# MCU.net
KiCad netlist of a schematic drawn in Altium Designer
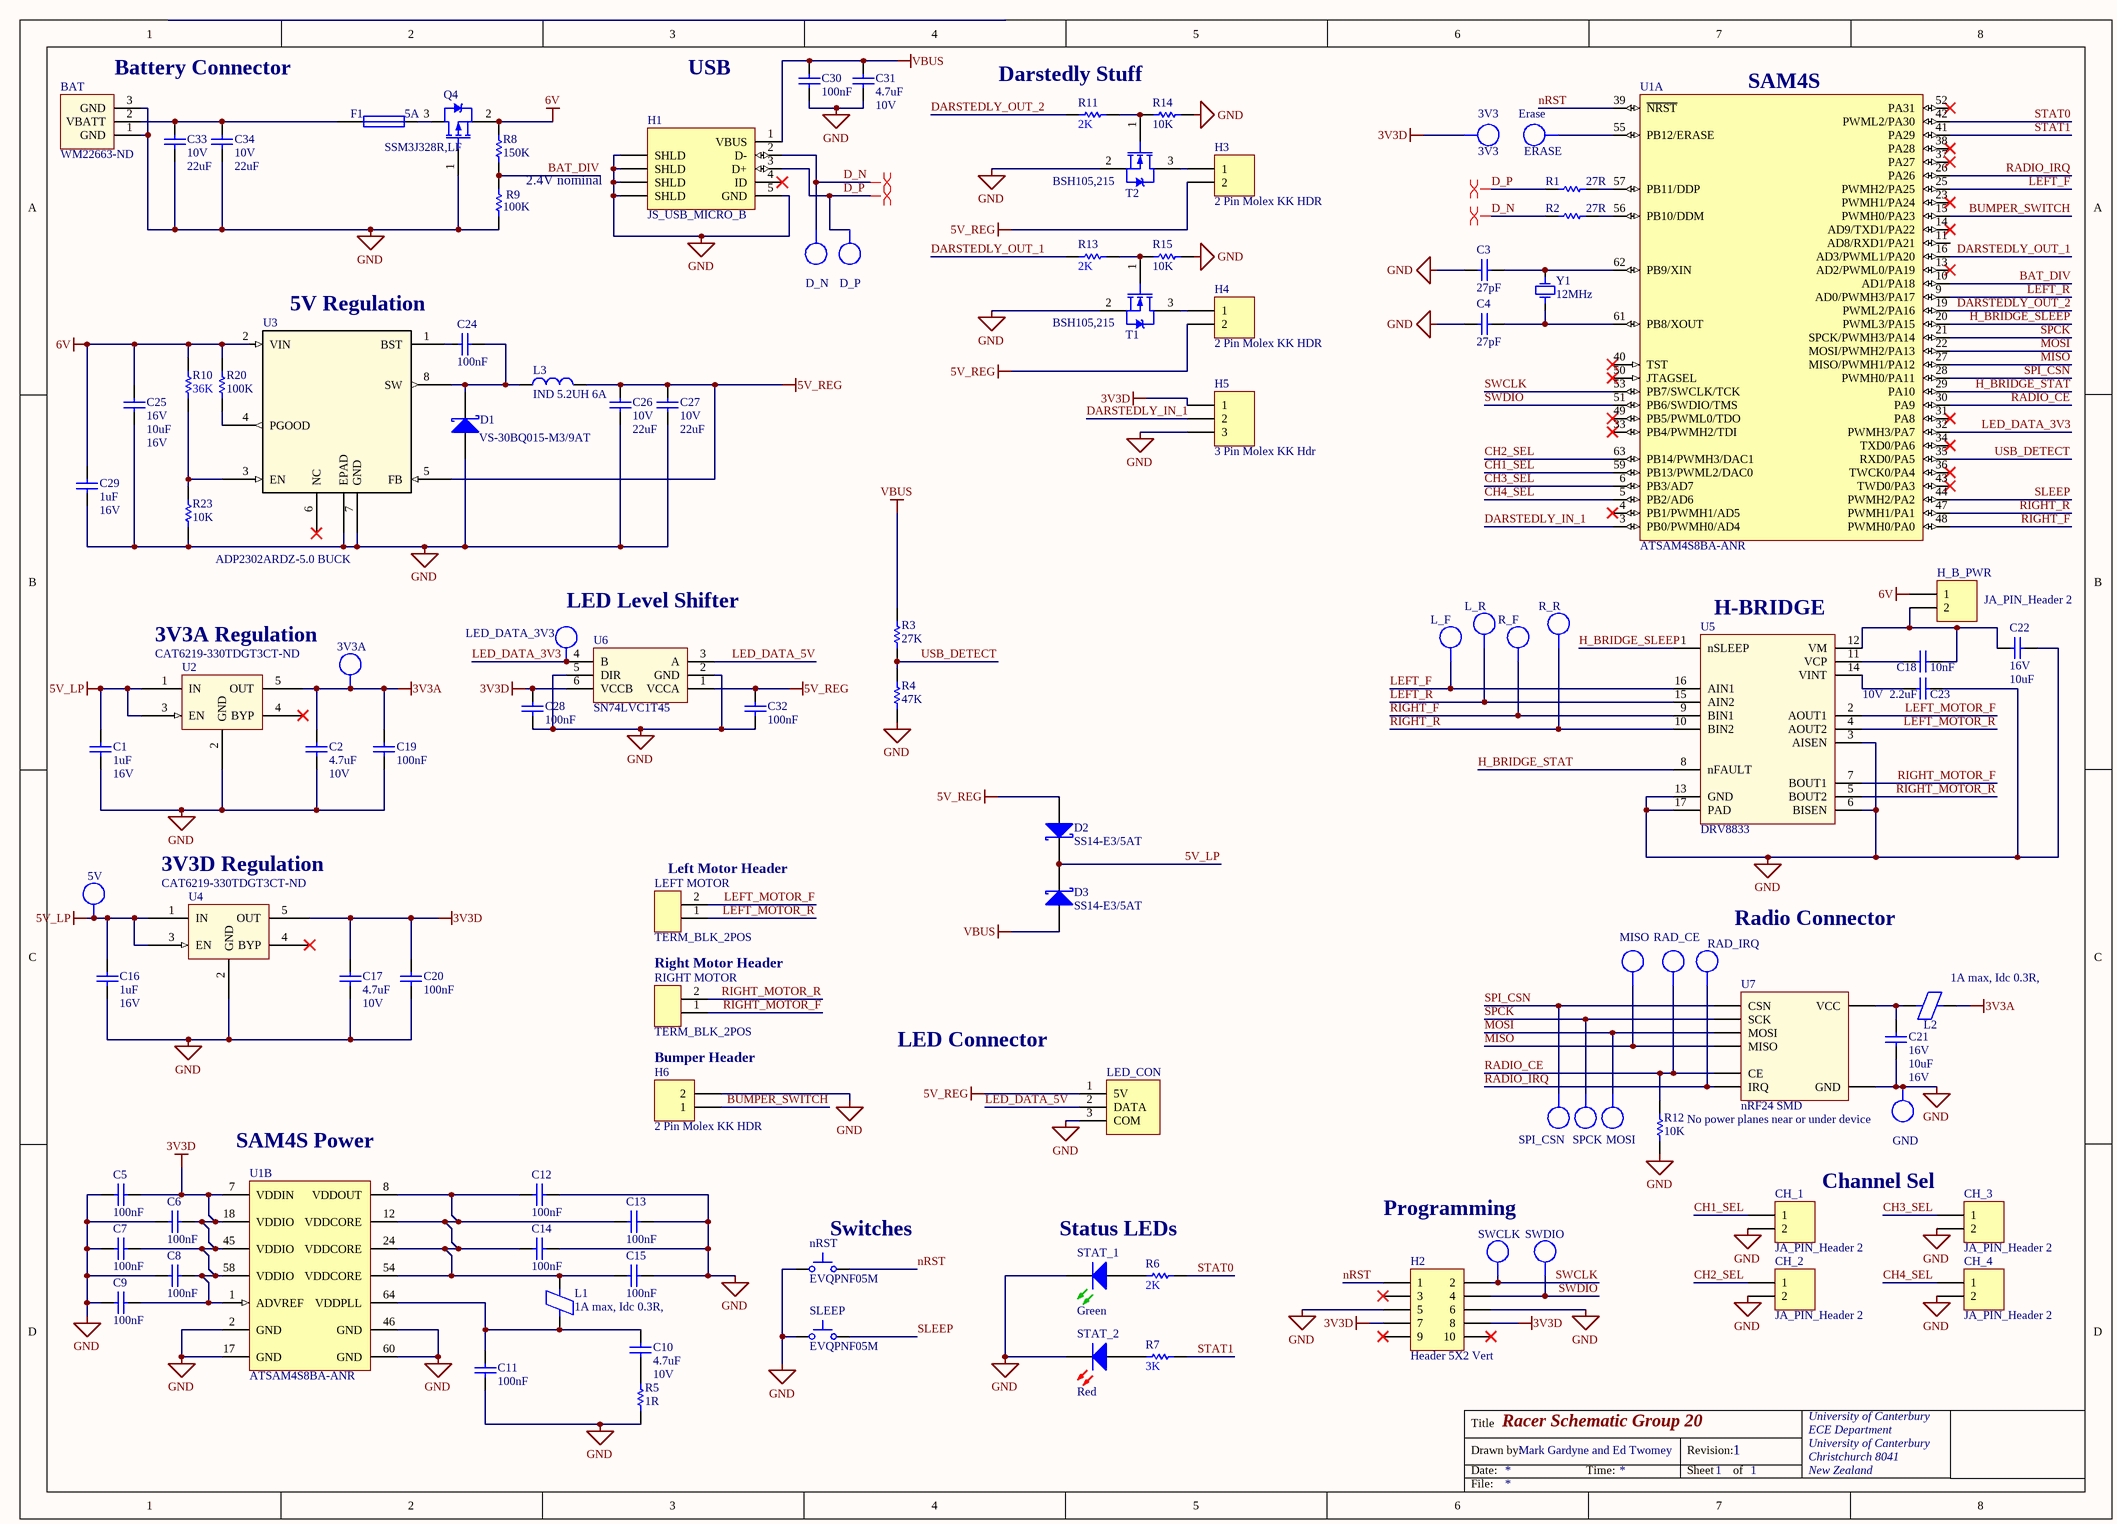
[diagram p0: MCU.SchDoc]

(export (version "E")
  (design (tool "Eeschema 10.0.6"))
  (components
    (comp (ref "3V3")
      (value "3V3")
      (footprint "TP_1206")
      (description "Test-Point 3.3x1.6x2.1mm SMD")
      (fields
        (field (name "MANUFACTURER") "Harwin Inc")
        (field (name "MANUFACTURER PART NUMBER") "S1751-46R")
      )
      (libsource (lib "ECE AD19Components_22V1") (part "TP_1206"))
    )
    (comp (ref "3V3A")
      (value "TP")
      (footprint "TP_1206")
      (description "Test-Point 3.3x1.6x2.1mm SMD")
      (fields
        (field (name "MANUFACTURER") "Harwin Inc")
        (field (name "MANUFACTURER PART NUMBER") "S1751-46R")
      )
      (libsource (lib "ECE AD19Components_22V1") (part "TP_1206"))
    )
    (comp (ref "5V")
      (value "TP")
      (footprint "TP_1206")
      (description "Test-Point 3.3x1.6x2.1mm SMD")
      (fields
        (field (name "MANUFACTURER") "Harwin Inc")
        (field (name "MANUFACTURER PART NUMBER") "S1751-46R")
      )
      (libsource (lib "ECE AD19Components_22V1") (part "TP_1206"))
    )
    (comp (ref "BAT")
      (value "Battery_HEADER_3pin")
      (footprint "BATT_HEADER_3POS")
      (description "3Pin Header 2.54mm spacing\r\nDigikey #WM22663-ND")
      (fields (field (name "SUPPLIER PART NUMBER 1") "WM22663-ND"))
      (libsource (lib "ENCE461AD19_V22") (part "Battery_HEADER_3pin"))
    )
    (comp (ref "C1")
      (value "1uF")
      (footprint "CAPC1608L")
      (description "CAP CER 1uF Y5V -20% +80% 16V 0603")
      (fields (field (name "MAX VOLTAGE") "16V"))
      (libsource (lib "ECE AD19Components_22V1") (part "CC_1uF_0603"))
    )
    (comp (ref "C2")
      (value "4.7uF")
      (footprint "CAPC1608N")
      (description "CAP CER 4.7uF X5R +-20%  10V 0603")
      (fields (field (name "MAX VOLTAGE") "10V"))
      (libsource (lib "ECE AD19Components_22V1") (part "CC_4.7uF_0603"))
    )
    (comp (ref "C3")
      (value "27pF")
      (footprint "CAPC1608L")
      (description "CAP CER 27pF NPO/COG +-5% 50V 0603")
      (libsource (lib "ECE AD19Components_22V1") (part "CC_27pF_0603"))
    )
    (comp (ref "C4")
      (value "27pF")
      (footprint "CAPC1608L")
      (description "CAP CER 27pF NPO/COG +-5% 50V 0603")
      (libsource (lib "ECE AD19Components_22V1") (part "CC_27pF_0603"))
    )
    (comp (ref "C5")
      (value "100nF")
      (footprint "CAPC1608L")
      (description "CAP CER 100nF X7R +-10% 50V 0603")
      (libsource (lib "ECE AD19Components_22V1") (part "CC_100nF_0603"))
    )
    (comp (ref "C6")
      (value "100nF")
      (footprint "CAPC1608L")
      (description "CAP CER 100nF X7R +-10% 50V 0603")
      (libsource (lib "ECE AD19Components_22V1") (part "CC_100nF_0603"))
    )
    (comp (ref "C7")
      (value "100nF")
      (footprint "CAPC1608L")
      (description "CAP CER 100nF X7R +-10% 50V 0603")
      (libsource (lib "ECE AD19Components_22V1") (part "CC_100nF_0603"))
    )
    (comp (ref "C8")
      (value "100nF")
      (footprint "CAPC1608L")
      (description "CAP CER 100nF X7R +-10% 50V 0603")
      (libsource (lib "ECE AD19Components_22V1") (part "CC_100nF_0603"))
    )
    (comp (ref "C9")
      (value "100nF")
      (footprint "CAPC1608L")
      (description "CAP CER 100nF X7R +-10% 50V 0603")
      (libsource (lib "ECE AD19Components_22V1") (part "CC_100nF_0603"))
    )
    (comp (ref "C10")
      (value "4.7uF")
      (footprint "CAPC1608N")
      (description "CAP CER 4.7uF X5R +-20%  10V 0603")
      (fields (field (name "MAX VOLTAGE") "10V"))
      (libsource (lib "ECE AD19Components_22V1") (part "CC_4.7uF_0603"))
    )
    (comp (ref "C11")
      (value "100nF")
      (footprint "CAPC1608L")
      (description "CAP CER 100nF X7R +-10% 50V 0603")
      (libsource (lib "ECE AD19Components_22V1") (part "CC_100nF_0603"))
    )
    (comp (ref "C12")
      (value "100nF")
      (footprint "CAPC1608L")
      (description "CAP CER 100nF X7R +-10% 50V 0603")
      (libsource (lib "ECE AD19Components_22V1") (part "CC_100nF_0603"))
    )
    (comp (ref "C13")
      (value "100nF")
      (footprint "CAPC1608L")
      (description "CAP CER 100nF X7R +-10% 50V 0603")
      (libsource (lib "ECE AD19Components_22V1") (part "CC_100nF_0603"))
    )
    (comp (ref "C14")
      (value "100nF")
      (footprint "CAPC1608L")
      (description "CAP CER 100nF X7R +-10% 50V 0603")
      (libsource (lib "ECE AD19Components_22V1") (part "CC_100nF_0603"))
    )
    (comp (ref "C15")
      (value "100nF")
      (footprint "CAPC1608L")
      (description "CAP CER 100nF X7R +-10% 50V 0603")
      (libsource (lib "ECE AD19Components_22V1") (part "CC_100nF_0603"))
    )
    (comp (ref "C16")
      (value "1uF")
      (footprint "CAPC1608L")
      (description "CAP CER 1uF Y5V -20% +80% 16V 0603")
      (fields (field (name "MAX VOLTAGE") "16V"))
      (libsource (lib "ECE AD19Components_22V1") (part "CC_1uF_0603"))
    )
    (comp (ref "C17")
      (value "4.7uF")
      (footprint "CAPC1608N")
      (description "CAP CER 4.7uF X5R +-20%  10V 0603")
      (fields (field (name "MAX VOLTAGE") "10V"))
      (libsource (lib "ECE AD19Components_22V1") (part "CC_4.7uF_0603"))
    )
    (comp (ref "C18")
      (value "10nF")
      (footprint "CAPC1608L")
      (description "CAP CER 10nF X7R +-10% 50V 0603")
      (libsource (lib "ECE AD19Components_22V1") (part "CC_10nF_0603"))
    )
    (comp (ref "C19")
      (value "100nF")
      (footprint "CAPC1608L")
      (description "CAP CER 100nF X7R +-10% 50V 0603")
      (libsource (lib "ECE AD19Components_22V1") (part "CC_100nF_0603"))
    )
    (comp (ref "C20")
      (value "100nF")
      (footprint "CAPC1608L")
      (description "CAP CER 100nF X7R +-10% 50V 0603")
      (libsource (lib "ECE AD19Components_22V1") (part "CC_100nF_0603"))
    )
    (comp (ref "C21")
      (value "10uF")
      (footprint "CAPC2012L")
      (description "CAP CER 10uF X5R 16V 0805")
      (fields
        (field (name "MANUFACTURER") "Samsung Electro-Mechanics")
        (field (name "MANUFACTURER PART NUMBER") "CL21A106KOQNNWE")
        (field (name "VOLTAGE - RATED") "16V")
        (field (name "MAX VOLTAGE") "16V")
      )
      (libsource (lib "ECE AD19Components_22V1") (part "CC_10uF_0805_16V"))
    )
    (comp (ref "C22")
      (value "10uF")
      (footprint "CAPC2012L")
      (description "CAP CER 10uF X5R 16V 0805")
      (fields
        (field (name "MANUFACTURER") "Samsung Electro-Mechanics")
        (field (name "MANUFACTURER PART NUMBER") "CL21A106KOQNNWE")
        (field (name "VOLTAGE - RATED") "16V")
      )
      (libsource (lib "ECE AD19Components_22V1") (part "CC_10uF_0805_16V"))
    )
    (comp (ref "C23")
      (value "2.2uF")
      (footprint "CAPC1608L")
      (description "CAP CER 2.2uF X5R +-20% 10V 0603")
      (fields (field (name "MAX VOLTAGE") "10V"))
      (libsource (lib "ECE AD19Components_22V1") (part "CC_2.2uF_0603"))
    )
    (comp (ref "C24")
      (value "100nF")
      (footprint "CAPC1608L")
      (description "CAP CER 100nF X7R +-10% 50V 0603")
      (libsource (lib "ECE AD19Components_22V1") (part "CC_100nF_0603"))
    )
    (comp (ref "C25")
      (value "10uF")
      (footprint "CAPC2012L")
      (description "CAP CER 10uF X5R 16V 0805")
      (fields
        (field (name "MANUFACTURER") "Samsung Electro-Mechanics")
        (field (name "MANUFACTURER PART NUMBER") "CL21A106KOQNNWE")
        (field (name "VOLTAGE - RATED") "16V")
        (field (name "MAX VOLTAGE") "16V")
      )
      (libsource (lib "ECE AD19Components_22V1") (part "CC_10uF_0805_16V"))
    )
    (comp (ref "C26")
      (value "22uF")
      (footprint "CAPC3216L")
      (description "CAP CER 22uF Y5V -20% +80% 10V 1206")
      (fields (field (name "MAX VOLTAGE") "10V"))
      (libsource (lib "ECE AD19Components_22V1") (part "CC_22uF_1206"))
    )
    (comp (ref "C27")
      (value "22uF")
      (footprint "CAPC3216L")
      (description "CAP CER 22uF Y5V -20% +80% 10V 1206")
      (fields (field (name "MAX VOLTAGE") "10V"))
      (libsource (lib "ECE AD19Components_22V1") (part "CC_22uF_1206"))
    )
    (comp (ref "C28")
      (value "100nF")
      (footprint "CAPC1608L")
      (description "CAP CER 100nF X7R +-10% 50V 0603")
      (libsource (lib "ECE AD19Components_22V1") (part "CC_100nF_0603"))
    )
    (comp (ref "C29")
      (value "1uF")
      (footprint "CAPC1608L")
      (description "CAP CER 1uF Y5V -20% +80% 16V 0603")
      (fields (field (name "MAX VOLTAGE") "16V"))
      (libsource (lib "ECE AD19Components_22V1") (part "CC_1uF_0603"))
    )
    (comp (ref "C30")
      (value "100nF")
      (footprint "CAPC1608L")
      (description "CAP CER 100nF X7R +-10% 50V 0603")
      (libsource (lib "ECE AD19Components_22V1") (part "CC_100nF_0603"))
    )
    (comp (ref "C31")
      (value "4.7uF")
      (footprint "CAPC1608N")
      (description "CAP CER 4.7uF X5R +-20%  10V 0603")
      (fields (field (name "MAX VOLTAGE") "10V"))
      (libsource (lib "ECE AD19Components_22V1") (part "CC_4.7uF_0603"))
    )
    (comp (ref "C32")
      (value "100nF")
      (footprint "CAPC1608L")
      (description "CAP CER 100nF X7R +-10% 50V 0603")
      (libsource (lib "ECE AD19Components_22V1") (part "CC_100nF_0603"))
    )
    (comp (ref "C33")
      (value "22uF")
      (footprint "CAPC3216L")
      (description "CAP CER 22uF Y5V -20% +80% 10V 1206")
      (fields (field (name "MAX VOLTAGE") "10V"))
      (libsource (lib "ECE AD19Components_22V1") (part "CC_22uF_1206"))
    )
    (comp (ref "C34")
      (value "22uF")
      (footprint "CAPC3216L")
      (description "CAP CER 22uF Y5V -20% +80% 10V 1206")
      (fields (field (name "MAX VOLTAGE") "10V"))
      (libsource (lib "ECE AD19Components_22V1") (part "CC_22uF_1206"))
    )
    (comp (ref "CH_1")
      (value "JA_PIN_Header 2")
      (footprint "HDR1X2")
      (description "Header, 2-Pin")
      (fields (field (name "PUBLISHER") "Altium Limited"))
      (libsource (lib "ECE AD19Components_22V1") (part "JA_PIN_Header 2"))
    )
    (comp (ref "CH_2")
      (value "JA_PIN_Header 2")
      (footprint "HDR1X2")
      (description "Header, 2-Pin")
      (fields (field (name "PUBLISHER") "Altium Limited"))
      (libsource (lib "ECE AD19Components_22V1") (part "JA_PIN_Header 2"))
    )
    (comp (ref "CH_3")
      (value "JA_PIN_Header 2")
      (footprint "HDR1X2")
      (description "Header, 2-Pin")
      (fields (field (name "PUBLISHER") "Altium Limited"))
      (libsource (lib "ECE AD19Components_22V1") (part "JA_PIN_Header 2"))
    )
    (comp (ref "CH_4")
      (value "JA_PIN_Header 2")
      (footprint "HDR1X2")
      (description "Header, 2-Pin")
      (fields (field (name "PUBLISHER") "Altium Limited"))
      (libsource (lib "ECE AD19Components_22V1") (part "JA_PIN_Header 2"))
    )
    (comp (ref "D1")
      (value "VS-30BQ015-M3/9AT")
      (footprint "SMC")
      (description "DIODE, SCHOTTKY, 3A, 15V, DO-214AB / SMC")
      (fields (field (name "MANUFACTURER") "Vishay Semiconductors"))
      (libsource (lib "ECE AD19Components_22V1") (part "DS_VS-30BQ015-M3"))
    )
    (comp (ref "D2")
      (value "SS14-E3/5AT")
      (footprint "DIOM4227X23N")
      (description "DIODE, SCHOTTKY, 1A, 40V, DO-214AC")
      (fields
        (field (name "MANUFACTURER") "VISHAY GENERAL SEMICONDUCTOR")
        (field (name "MANUFACTURER PART NUMBER") "SS14-E3/5AT")
      )
      (libsource (lib "ECE AD19Components_22V1") (part "DS_SS14E3"))
    )
    (comp (ref "D3")
      (value "SS14-E3/5AT")
      (footprint "DIOM4227X23N")
      (description "DIODE, SCHOTTKY, 1A, 40V, DO-214AC")
      (fields
        (field (name "MANUFACTURER") "VISHAY GENERAL SEMICONDUCTOR")
        (field (name "MANUFACTURER PART NUMBER") "SS14-E3/5AT")
      )
      (libsource (lib "ECE AD19Components_22V1") (part "DS_SS14E3"))
    )
    (comp (ref "D_N")
      (value "TP")
      (footprint "TP_1206")
      (description "Test-Point 3.3x1.6x2.1mm SMD")
      (fields
        (field (name "MANUFACTURER") "Harwin Inc")
        (field (name "MANUFACTURER PART NUMBER") "S1751-46R")
      )
      (libsource (lib "ECE AD19Components_22V1") (part "TP_1206"))
    )
    (comp (ref "D_P")
      (value "TP")
      (footprint "TP_1206")
      (description "Test-Point 3.3x1.6x2.1mm SMD")
      (fields
        (field (name "MANUFACTURER") "Harwin Inc")
        (field (name "MANUFACTURER PART NUMBER") "S1751-46R")
      )
      (libsource (lib "ECE AD19Components_22V1") (part "TP_1206"))
    )
    (comp (ref "ERASE")
      (value "Erase")
      (footprint "TP_1206")
      (description "Test-Point 3.3x1.6x2.1mm SMD")
      (fields
        (field (name "MANUFACTURER") "Harwin Inc")
        (field (name "MANUFACTURER PART NUMBER") "S1751-46R")
      )
      (libsource (lib "ECE AD19Components_22V1") (part "TP_1206"))
    )
    (comp (ref "F1")
      (value "5A")
      (footprint "RESC3216N")
      (description "Fuse 5.0A Fast Acting 1206 SMD")
      (fields (field (name "MANUFACTURER PART NUMBER") "C1F5") (field (name "MANUFACTURER") "Bel TRP"))
      (libsource (lib "ECE AD19Components_22V1") (part "FS_Fuse_5.0A"))
    )
    (comp (ref "GND")
      (value "TP")
      (footprint "TP_1206")
      (description "Test-Point 3.3x1.6x2.1mm SMD")
      (fields
        (field (name "MANUFACTURER") "Harwin Inc")
        (field (name "MANUFACTURER PART NUMBER") "S1751-46R")
      )
      (libsource (lib "ECE AD19Components_22V1") (part "TP_1206"))
    )
    (comp (ref "H1")
      (value "JS_USB_MICRO_B")
      (footprint "FCI_USB_10118194-0001LF")
      (description "CONN USB MICRO B RECPT SMT R/A")
      (fields (field (name "MANUFACTURER") "FCI") (field (name "MANUFACTURER PART NUMBER") "10118194-0001LF"))
      (libsource (lib "ECE AD19Components_22V1") (part "JS_USB_MICRO_B_SMT"))
    )
    (comp (ref "H2")
      (value "Header 5X2 Vert")
      (footprint "IDC2.54-V10D")
      (description "IDC Header, 2,54mm, 10-Pin, Vert")
      (libsource (lib "ECE AD19Components_22V1") (part "JA_HDR_IDC_5X2_VERT"))
    )
    (comp (ref "H3")
      (value "2 Pin Molex KK HDR")
      (footprint "MOLEX_KK_2_HDR")
      (description "CONN HEADER 2POS 2.54mm VERT_Thru Hole")
      (libsource (lib "") (part "JA_MOLEX_KK_2POS_1"))
    )
    (comp (ref "H4")
      (value "2 Pin Molex KK HDR")
      (footprint "MOLEX_KK_2_HDR")
      (description "CONN HEADER 2POS 2.54mm VERT_Thru Hole")
      (libsource (lib "") (part "JA_MOLEX_KK_2POS_1"))
    )
    (comp (ref "H5")
      (value "3 Pin Molex KK Hdr")
      (footprint "MOLEX_KK_3_HDR")
      (description "CONN HEADER 3POS 2.54mm VERT_Thru Hole")
      (fields (field (name "MANUFACTURER") "Molex"))
      (libsource (lib "ECE AD19Components_22V1") (part "JA_MOLEX_KK_3POS"))
    )
    (comp (ref "H6")
      (value "2 Pin Molex KK HDR")
      (footprint "MOLEX_KK_2_HDR")
      (description "CONN HEADER 2POS 2.54mm VERT_Thru Hole")
      (libsource (lib "ECE AD19Components_22V1") (part "JA_MOLEX_KK_2POS"))
    )
    (comp (ref "H_B_PWR")
      (value "JA_PIN_Header 2")
      (footprint "HDR1X2")
      (description "Header, 2-Pin")
      (fields (field (name "PUBLISHER") "Altium Limited"))
      (libsource (lib "ECE AD19Components_22V1") (part "JA_PIN_Header 2"))
    )
    (comp (ref "L1")
      (value "1A max, Idc 0.3R,")
      (footprint "INDC3216L")
      (description "Ferrite Bead, Rdc 0.3R, Z100MHZ 600R, Imax 1A, SMD 1206")
      (fields
        (field (name "MANUFACTURER") "FAIR-RITE")
        (field (name "MANUFACTURER PART NUMBER") "2512066017Y1")
      )
      (libsource (lib "ECE AD19Components_22V1") (part "IN_Ferrite-Bead"))
    )
    (comp (ref "L2")
      (value "1A max, Idc 0.3R,")
      (footprint "INDC3216L")
      (description "Ferrite Bead, Rdc 0.3R, Z100MHZ 600R, Imax 1A, SMD 1206")
      (fields
        (field (name "MANUFACTURER") "FAIR-RITE")
        (field (name "MANUFACTURER PART NUMBER") "2512066017Y1")
      )
      (libsource (lib "ECE AD19Components_22V1") (part "IN_Ferrite-Bead"))
    )
    (comp (ref "L3")
      (value "IND 5.2UH 6A")
      (footprint "INDUCTOR5u2")
      (description "FIXED IND 5.2UH 6A 22 MOHM SMD")
      (fields
        (field (name "MANUFACTURER") "Sumida America Components Inc.")
        (field (name "MANUFACTURER PART NUMBER") "CDRH104RNP-5R2NC")
      )
      (libsource (lib "ENCE461AD19_V22") (part "CDRH104RNP-5R2NC"))
    )
    (comp (ref "LED_CON")
      (value "3 Pin Molex KK Hdr")
      (footprint "MOLEX_KK_3_HDR")
      (description "CONN HEADER 3POS 2.54mm VERT_Thru Hole")
      (fields (field (name "MANUFACTURER") "Molex"))
      (libsource (lib "ENCE461AD19_V22") (part "LED_Strip_Header"))
    )
    (comp (ref "LED_DATA_3V3")
      (value "TP")
      (footprint "TP_1206")
      (description "Test-Point 3.3x1.6x2.1mm SMD")
      (fields
        (field (name "MANUFACTURER") "Harwin Inc")
        (field (name "MANUFACTURER PART NUMBER") "S1751-46R")
      )
      (libsource (lib "ECE AD19Components_22V1") (part "TP_1206"))
    )
    (comp (ref "LEFT MOTOR")
      (value "TERM_BLK_2POS")
      (footprint "TERM_BLK_2POS")
      (description "2 Position Terminal Block 7.62mm spacing")
      (libsource (lib "ENCE461AD19_V22") (part "TERM_BLK_2POS"))
    )
    (comp (ref "L_F")
      (value "TP")
      (footprint "TP_1206")
      (description "Test-Point 3.3x1.6x2.1mm SMD")
      (fields
        (field (name "MANUFACTURER") "Harwin Inc")
        (field (name "MANUFACTURER PART NUMBER") "S1751-46R")
      )
      (libsource (lib "ECE AD19Components_22V1") (part "TP_1206"))
    )
    (comp (ref "L_R")
      (value "TP")
      (footprint "TP_1206")
      (description "Test-Point 3.3x1.6x2.1mm SMD")
      (fields
        (field (name "MANUFACTURER") "Harwin Inc")
        (field (name "MANUFACTURER PART NUMBER") "S1751-46R")
      )
      (libsource (lib "ECE AD19Components_22V1") (part "TP_1206"))
    )
    (comp (ref "MISO")
      (value "TP")
      (footprint "TP_1206")
      (description "Test-Point 3.3x1.6x2.1mm SMD")
      (fields
        (field (name "MANUFACTURER") "Harwin Inc")
        (field (name "MANUFACTURER PART NUMBER") "S1751-46R")
      )
      (libsource (lib "ECE AD19Components_22V1") (part "TP_1206"))
    )
    (comp (ref "MOSI")
      (value "TP")
      (footprint "TP_1206")
      (description "Test-Point 3.3x1.6x2.1mm SMD")
      (fields
        (field (name "MANUFACTURER") "Harwin Inc")
        (field (name "MANUFACTURER PART NUMBER") "S1751-46R")
      )
      (libsource (lib "ECE AD19Components_22V1") (part "TP_1206"))
    )
    (comp (ref "nRST")
      (value "EVQPNF05M")
      (footprint "EVQPNF05M")
      (description "Panasonic 6 x 3.5mm SMD Light Touch Switch Type SMD")
      (fields (field (name "MANUFACTURER") "Panasonic"))
      (libsource (lib "ECE AD19Components_22V1") (part "WS_EVQPNF05M"))
    )
    (comp (ref "Q4")
      (value "SSM3J328R,LF")
      (footprint "SOT23_L")
      (description "MOSFET P-CH 20V 6A SOT23-3")
      (fields
        (field (name "MANUFACTURER") "Toshiba")
        (field (name "MANUFACTURER PART NUMBER") "SSM3J328R,LF")
      )
      (libsource (lib "ECE AD19Components_22V1") (part "TM_SSM3J328R"))
    )
    (comp (ref "R1")
      (value "27R")
      (footprint "RESC1608L")
      (description "RES 27 OHM 1/10W 5% 0603 SMD")
      (libsource (lib "ECE AD19Components_22V1") (part "RS_27R"))
    )
    (comp (ref "R2")
      (value "27R")
      (footprint "RESC1608L")
      (description "RES 27 OHM 1/10W 5% 0603 SMD")
      (libsource (lib "ECE AD19Components_22V1") (part "RS_27R"))
    )
    (comp (ref "R3")
      (value "27K")
      (footprint "RESC1608L")
      (description "RES 27K OHM 1/10W 5% 0603 SMD")
      (libsource (lib "ECE AD19Components_22V1") (part "RS_27K"))
    )
    (comp (ref "R4")
      (value "47K")
      (footprint "RESC1608N")
      (description "RES 47.0K OHM 1/10W 5% 0603 SMD")
      (libsource (lib "ECE AD19Components_22V1") (part "RS_47K"))
    )
    (comp (ref "R5")
      (value "1R")
      (footprint "RESC3216L")
      (description "RES 1R OHM 1/4W 5% 1206 SMD")
      (libsource (lib "ECE AD19Components_22V1") (part "RT_1R"))
    )
    (comp (ref "R6")
      (value "2K")
      (footprint "RESC1608L")
      (description "RES 2K OHM 1/10W 5% 0603 SMD")
      (libsource (lib "ECE AD19Components_22V1") (part "RS_2K"))
    )
    (comp (ref "R7")
      (value "3K")
      (footprint "RESC1608L")
      (description "RES 3K OHM 1/10W 5% 0603 SMD")
      (libsource (lib "ECE AD19Components_22V1") (part "RS_3K"))
    )
    (comp (ref "R8")
      (value "150K")
      (footprint "RESC1608L")
      (description "RES 150K OHM 1/10W 5% 0603 SMD")
      (libsource (lib "ECE AD19Components_22V1") (part "RS_150K"))
    )
    (comp (ref "R9")
      (value "100K")
      (footprint "RESC1608L")
      (description "RES 100K OHM 1/10W 5% 0603 SMD")
      (libsource (lib "ECE AD19Components_22V1") (part "RS_100K"))
    )
    (comp (ref "R10")
      (value "36K")
      (footprint "RESC1608L")
      (description "RES 36K OHM 1/10W 5% 0603 SMD")
      (libsource (lib "ECE AD19Components_22V1") (part "RS_36K"))
    )
    (comp (ref "R11")
      (value "2K")
      (footprint "RESC1608L")
      (description "RES 2K OHM 1/10W 5% 0603 SMD")
      (libsource (lib "ECE AD19Components_22V1") (part "RS_2K"))
    )
    (comp (ref "R12")
      (value "10K")
      (footprint "RESC1608L")
      (description "RES 10.0K OHM 1/10W 5% 0603 SMD")
      (libsource (lib "ECE AD19Components_22V1") (part "RS_10K"))
    )
    (comp (ref "R13")
      (value "2K")
      (footprint "RESC1608L")
      (description "RES 2K OHM 1/10W 5% 0603 SMD")
      (libsource (lib "ECE AD19Components_22V1") (part "RS_2K"))
    )
    (comp (ref "R14")
      (value "10K")
      (footprint "RESC1608L")
      (description "RES 10.0K OHM 1/10W 5% 0603 SMD")
      (libsource (lib "ECE AD19Components_22V1") (part "RS_10K"))
    )
    (comp (ref "R15")
      (value "10K")
      (footprint "RESC1608L")
      (description "RES 10.0K OHM 1/10W 5% 0603 SMD")
      (libsource (lib "ECE AD19Components_22V1") (part "RS_10K"))
    )
    (comp (ref "R20")
      (value "100K")
      (footprint "RESC1608L")
      (description "RES 100K OHM 1/10W 5% 0603 SMD")
      (libsource (lib "ECE AD19Components_22V1") (part "RS_100K"))
    )
    (comp (ref "R23")
      (value "10K")
      (footprint "RESC1608L")
      (description "RES 10.0K OHM 1/10W 5% 0603 SMD")
      (libsource (lib "ECE AD19Components_22V1") (part "RS_10K"))
    )
    (comp (ref "RAD_CE")
      (value "TP")
      (footprint "TP_1206")
      (description "Test-Point 3.3x1.6x2.1mm SMD")
      (fields
        (field (name "MANUFACTURER") "Harwin Inc")
        (field (name "MANUFACTURER PART NUMBER") "S1751-46R")
      )
      (libsource (lib "ECE AD19Components_22V1") (part "TP_1206"))
    )
    (comp (ref "RAD_IRQ")
      (value "TP")
      (footprint "TP_1206")
      (description "Test-Point 3.3x1.6x2.1mm SMD")
      (fields
        (field (name "MANUFACTURER") "Harwin Inc")
        (field (name "MANUFACTURER PART NUMBER") "S1751-46R")
      )
      (libsource (lib "ECE AD19Components_22V1") (part "TP_1206"))
    )
    (comp (ref "RIGHT MOTOR")
      (value "TERM_BLK_2POS")
      (footprint "TERM_BLK_2POS")
      (description "2 Position Terminal Block 7.62mm spacing")
      (libsource (lib "ENCE461AD19_V22") (part "TERM_BLK_2POS"))
    )
    (comp (ref "R_F")
      (value "TP")
      (footprint "TP_1206")
      (description "Test-Point 3.3x1.6x2.1mm SMD")
      (fields
        (field (name "MANUFACTURER") "Harwin Inc")
        (field (name "MANUFACTURER PART NUMBER") "S1751-46R")
      )
      (libsource (lib "ECE AD19Components_22V1") (part "TP_1206"))
    )
    (comp (ref "R_R")
      (value "TP")
      (footprint "TP_1206")
      (description "Test-Point 3.3x1.6x2.1mm SMD")
      (fields
        (field (name "MANUFACTURER") "Harwin Inc")
        (field (name "MANUFACTURER PART NUMBER") "S1751-46R")
      )
      (libsource (lib "ECE AD19Components_22V1") (part "TP_1206"))
    )
    (comp (ref "SLEEP")
      (value "EVQPNF05M")
      (footprint "EVQPNF05M")
      (description "Panasonic 6 x 3.5mm SMD Light Touch Switch Type SMD")
      (fields (field (name "MANUFACTURER") "Panasonic"))
      (libsource (lib "ECE AD19Components_22V1") (part "WS_EVQPNF05M"))
    )
    (comp (ref "SPCK")
      (value "TP")
      (footprint "TP_1206")
      (description "Test-Point 3.3x1.6x2.1mm SMD")
      (fields
        (field (name "MANUFACTURER") "Harwin Inc")
        (field (name "MANUFACTURER PART NUMBER") "S1751-46R")
      )
      (libsource (lib "ECE AD19Components_22V1") (part "TP_1206"))
    )
    (comp (ref "SPI_CSN")
      (value "TP")
      (footprint "TP_1206")
      (description "Test-Point 3.3x1.6x2.1mm SMD")
      (fields
        (field (name "MANUFACTURER") "Harwin Inc")
        (field (name "MANUFACTURER PART NUMBER") "S1751-46R")
      )
      (libsource (lib "ECE AD19Components_22V1") (part "TP_1206"))
    )
    (comp (ref "STAT_1")
      (value "Green")
      (footprint "WL-SMCW0603")
      (description "LED Green 430mcd 0603 SMD")
      (fields
        (field (name "MANUFACTURER") "WURTH ELEKTRONIK")
        (field (name "MANUFACTURER PART NUMBER") "150060GS75000")
        (field (name "LED COLOUR") "Green")
      )
      (libsource (lib "ECE AD19Components_22V1") (part "DL_150060GS75000"))
    )
    (comp (ref "STAT_2")
      (value "Red")
      (footprint "WL-SMCW0603")
      (description "LED Red 250mcd 0603 SMD")
      (fields
        (field (name "MANUFACTURER") "WURTH ELEKTRONIK")
        (field (name "MANUFACTURER PART NUMBER") "150060RS75000")
        (field (name "LED COLOUR") "Red")
      )
      (libsource (lib "ECE AD19Components_22V1") (part "DL_150060RS75000"))
    )
    (comp (ref "SWCLK")
      (value "TP")
      (footprint "TP_1206")
      (description "Test-Point 3.3x1.6x2.1mm SMD")
      (fields
        (field (name "MANUFACTURER") "Harwin Inc")
        (field (name "MANUFACTURER PART NUMBER") "S1751-46R")
      )
      (libsource (lib "ECE AD19Components_22V1") (part "TP_1206"))
    )
    (comp (ref "SWDIO")
      (value "TP")
      (footprint "TP_1206")
      (description "Test-Point 3.3x1.6x2.1mm SMD")
      (fields
        (field (name "MANUFACTURER") "Harwin Inc")
        (field (name "MANUFACTURER PART NUMBER") "S1751-46R")
      )
      (libsource (lib "ECE AD19Components_22V1") (part "TP_1206"))
    )
    (comp (ref "T1")
      (value "BSH105,215")
      (footprint "SOT23_L")
      (description "MOSFET N-CH 20V 1.05A SOT-23")
      (fields
        (field (name "MANUFACTURER") "NXP Semiconductors")
        (field (name "MANUFACTURER PART NUMBER") "BSH105,215")
      )
      (libsource (lib "ECE AD19Components_22V1") (part "TM_BSH105"))
    )
    (comp (ref "T2")
      (value "BSH105,215")
      (footprint "SOT23_L")
      (description "MOSFET N-CH 20V 1.05A SOT-23")
      (fields
        (field (name "MANUFACTURER") "NXP Semiconductors")
        (field (name "MANUFACTURER PART NUMBER") "BSH105,215")
      )
      (libsource (lib "ECE AD19Components_22V1") (part "TM_BSH105"))
    )
    (comp (ref "U1")
      (value "ATSAM4S8BA-ANR")
      (footprint "LQFP64_L")
      (description "IC MCU 32BIT 512KB FLASH 64LQFP")
      (fields (field (name "MANUFACTURER") "Atmel"))
      (libsource (lib "ECE AD19Components_22V1") (part "SE_ATSAM4S16BA-MU"))
    )
    (comp (ref "U2")
      (value "CAT6219-330TDGT3")
      (footprint "SOT95P280X145-5N")
      (description "IC REG LIN 3.3V 500MA TSOT23-5")
      (fields
        (field (name "BASE PART NUMBER") "CAT6219")
        (field (name "SUPPLIER PART NUMBER") "CAT6219-330TDGT3CT-ND")
      )
      (libsource (lib "ENCE461AD19_V22") (part "SV_CAT6219-330TDGT3"))
    )
    (comp (ref "U3")
      (value "ADP2302ARDZ-5.0 BUCK")
      (footprint "RD_8_1")
      (description "IC REG BUCK 5V 2A 8SOIC")
      (fields (field (name "MANUFACTURER_PART_NUMBER") "ADP2302ARDZ-5.0-R7"))
      (libsource (lib "ENCE461AD19_V22") (part "ADP2302ARDZ-5.0-R7"))
    )
    (comp (ref "U4")
      (value "CAT6219-330TDGT3")
      (footprint "SOT95P280X145-5N")
      (description "IC REG LIN 3.3V 500MA TSOT23-5")
      (fields
        (field (name "BASE PART NUMBER") "CAT6219")
        (field (name "SUPPLIER PART NUMBER") "CAT6219-330TDGT3CT-ND")
      )
      (libsource (lib "ENCE461AD19_V22") (part "SV_CAT6219-330TDGT3"))
    )
    (comp (ref "U5")
      (value "DRV8833")
      (footprint "HTSOP16 DRV8833")
      (description "Dual H-Bridge Motor Driver 1.5A")
      (libsource (lib "ENCE461AD19_V22") (part "DRV8833"))
    )
    (comp (ref "U6")
      (value "SN74LVC1T45")
      (footprint "SOT23-6_N")
      (description "1.8V - 5V level converter")
      (libsource (lib "ENCE461AD19_V22") (part "SN74LVC1T45"))
    )
    (comp (ref "U7")
      (value "nRF24 SMD")
      (footprint "NRF24")
      (description "nRF24 SMD Module")
      (fields (field (name "WARNING") "No power planes near or under device"))
      (libsource (lib "ENCE461AD19_V22") (part "NRF24"))
    )
    (comp (ref "Y1")
      (value "12MHz")
      (footprint "6.0X3.5-4")
      (description "CRYSTAL 12MHZ 18PF 6X3.5mm SMD")
      (fields
        (field (name "MANUFACTURER") "CTS-Frequency Controls")
        (field (name "MANUFACTURER PART NUMBER") "406C35D12M00000")
        (field (name "FREQUENCY") "12MHz")
      )
      (libsource (lib "ECE AD19Components_22V1") (part "XT_CRYSTAL_12MHz_18pF"))
    )
  )
  (nets
    (net (code "2") (name "/BAT_DIV") (class "Default")
      (node (ref "R8") (pin "1") (pinfunction "1_1") (pintype "passive"))
      (node (ref "R9") (pin "2") (pinfunction "2_2") (pintype "passive"))
      (node (ref "U1") (pin "10") (pinfunction "AD1/PA18_10") (pintype "bidirectional"))
    )
    (net (code "3") (name "/BUMPER_SWITCH") (class "Default")
      (node (ref "H6") (pin "1") (pinfunction "1_1") (pintype "passive"))
      (node (ref "U1") (pin "15") (pinfunction "PWMH0/PA23_15") (pintype "bidirectional"))
    )
    (net (code "4") (name "/CH1_SEL") (class "Default")
      (node (ref "CH_1") (pin "1") (pinfunction "1_1") (pintype "passive"))
      (node (ref "U1") (pin "59") (pinfunction "PB13/PWML2/DAC0_59") (pintype "bidirectional"))
    )
    (net (code "5") (name "/CH2_SEL") (class "Default")
      (node (ref "CH_2") (pin "1") (pinfunction "1_1") (pintype "passive"))
      (node (ref "U1") (pin "63") (pinfunction "PB14/PWMH3/DAC1_63") (pintype "bidirectional"))
    )
    (net (code "6") (name "/CH3_SEL") (class "Default")
      (node (ref "CH_3") (pin "1") (pinfunction "1_1") (pintype "passive"))
      (node (ref "U1") (pin "6") (pinfunction "PB3/AD7_6") (pintype "bidirectional"))
    )
    (net (code "7") (name "/CH4_SEL") (class "Default")
      (node (ref "CH_4") (pin "1") (pinfunction "1_1") (pintype "passive"))
      (node (ref "U1") (pin "5") (pinfunction "PB2/AD6_5") (pintype "bidirectional"))
    )
    (net (code "8") (name "/DARSTEDLY_IN_1") (class "Default")
      (node (ref "H5") (pin "2") (pinfunction "2_2") (pintype "passive"))
      (node (ref "U1") (pin "3") (pinfunction "PB0/PWMH0/AD4_3") (pintype "bidirectional"))
    )
    (net (code "9") (name "/DARSTEDLY_OUT_1") (class "Default")
      (node (ref "R13") (pin "1") (pinfunction "1_1") (pintype "passive"))
      (node (ref "U1") (pin "16") (pinfunction "AD3/PWML1/PA20_16") (pintype "bidirectional"))
    )
    (net (code "10") (name "/DARSTEDLY_OUT_2") (class "Default")
      (node (ref "R11") (pin "1") (pinfunction "1_1") (pintype "passive"))
      (node (ref "U1") (pin "19") (pinfunction "PWML2/PA16_19") (pintype "bidirectional"))
    )
    (net (code "11") (name "/D_N") (class "Default")
      (node (ref "D_N") (pin "1") (pinfunction "1_1") (pintype "passive"))
      (node (ref "H1") (pin "2") (pinfunction "D-_2") (pintype "bidirectional"))
      (node (ref "R2") (pin "1") (pinfunction "1_1") (pintype "passive"))
    )
    (net (code "12") (name "/D_P") (class "Default")
      (node (ref "D_P") (pin "1") (pinfunction "1_1") (pintype "passive"))
      (node (ref "H1") (pin "3") (pinfunction "D+_3") (pintype "bidirectional"))
      (node (ref "R1") (pin "1") (pinfunction "1_1") (pintype "passive"))
    )
    (net (code "13") (name "/H_BRIDGE_SLEEP") (class "Default")
      (node (ref "U1") (pin "20") (pinfunction "PWML3/PA15_20") (pintype "bidirectional"))
      (node (ref "U5") (pin "1") (pinfunction "nSLEEP_1") (pintype "passive"))
    )
    (net (code "14") (name "/H_BRIDGE_STAT") (class "Default")
      (node (ref "U1") (pin "29") (pinfunction "PA10_29") (pintype "bidirectional"))
      (node (ref "U5") (pin "8") (pinfunction "nFAULT_8") (pintype "passive"))
    )
    (net (code "15") (name "/LED_DATA_3V3") (class "Default")
      (node (ref "LED_DATA_3V3") (pin "1") (pinfunction "1_1") (pintype "passive"))
      (node (ref "U1") (pin "32") (pinfunction "PWMH3/PA7_32") (pintype "bidirectional"))
      (node (ref "U6") (pin "4") (pinfunction "B_4") (pintype "passive"))
    )
    (net (code "16") (name "/LED_DATA_5V") (class "Default")
      (node (ref "LED_CON") (pin "2") (pinfunction "DATA_2") (pintype "passive"))
      (node (ref "U6") (pin "3") (pinfunction "A_3") (pintype "passive"))
    )
    (net (code "17") (name "/LEFT_F") (class "Default")
      (node (ref "L_F") (pin "1") (pinfunction "1_1") (pintype "passive"))
      (node (ref "U1") (pin "25") (pinfunction "PWMH2/PA25_25") (pintype "bidirectional"))
      (node (ref "U5") (pin "16") (pinfunction "AIN1_16") (pintype "passive"))
    )
    (net (code "18") (name "/LEFT_MOTOR_F") (class "Default")
      (node (ref "LEFT MOTOR") (pin "2") (pintype "passive"))
      (node (ref "U5") (pin "2") (pinfunction "AOUT1_2") (pintype "passive"))
    )
    (net (code "19") (name "/LEFT_MOTOR_R") (class "Default")
      (node (ref "LEFT MOTOR") (pin "1") (pintype "passive"))
      (node (ref "U5") (pin "4") (pinfunction "AOUT2_4") (pintype "passive"))
    )
    (net (code "20") (name "/LEFT_R") (class "Default")
      (node (ref "L_R") (pin "1") (pinfunction "1_1") (pintype "passive"))
      (node (ref "U1") (pin "9") (pinfunction "AD0/PWMH3/PA17_9") (pintype "bidirectional"))
      (node (ref "U5") (pin "15") (pinfunction "AIN2_15") (pintype "passive"))
    )
    (net (code "21") (name "/MISO") (class "Default")
      (node (ref "MISO") (pin "1") (pinfunction "1_1") (pintype "passive"))
      (node (ref "U1") (pin "27") (pinfunction "MISO/PWMH1/PA12_27") (pintype "bidirectional"))
      (node (ref "U7") (pin "7") (pinfunction "MISO_7") (pintype "passive"))
    )
    (net (code "22") (name "/MOSI") (class "Default")
      (node (ref "MOSI") (pin "1") (pinfunction "1_1") (pintype "passive"))
      (node (ref "U1") (pin "22") (pinfunction "MOSI/PWMH2/PA13_22") (pintype "bidirectional"))
      (node (ref "U7") (pin "6") (pinfunction "MOSI_6") (pintype "passive"))
    )
    (net (code "23") (name "/RADIO_CE") (class "Default")
      (node (ref "R12") (pin "2") (pinfunction "2_2") (pintype "passive"))
      (node (ref "RAD_CE") (pin "1") (pinfunction "1_1") (pintype "passive"))
      (node (ref "U1") (pin "30") (pinfunction "PA9_30") (pintype "bidirectional"))
      (node (ref "U7") (pin "3") (pinfunction "CE_3") (pintype "passive"))
    )
    (net (code "24") (name "/RADIO_IRQ") (class "Default")
      (node (ref "RAD_IRQ") (pin "1") (pinfunction "1_1") (pintype "passive"))
      (node (ref "U1") (pin "26") (pinfunction "PA26_26") (pintype "bidirectional"))
      (node (ref "U7") (pin "8") (pinfunction "IRQ_8") (pintype "passive"))
    )
    (net (code "25") (name "/RIGHT_F") (class "Default")
      (node (ref "R_F") (pin "1") (pinfunction "1_1") (pintype "passive"))
      (node (ref "U1") (pin "48") (pinfunction "PWMH0/PA0_48") (pintype "bidirectional"))
      (node (ref "U5") (pin "9") (pinfunction "BIN1_9") (pintype "passive"))
    )
    (net (code "26") (name "/RIGHT_MOTOR_F") (class "Default")
      (node (ref "RIGHT MOTOR") (pin "1") (pintype "passive"))
      (node (ref "U5") (pin "7") (pinfunction "BOUT1_7") (pintype "passive"))
    )
    (net (code "27") (name "/RIGHT_MOTOR_R") (class "Default")
      (node (ref "RIGHT MOTOR") (pin "2") (pintype "passive"))
      (node (ref "U5") (pin "5") (pinfunction "BOUT2_5") (pintype "passive"))
    )
    (net (code "28") (name "/RIGHT_R") (class "Default")
      (node (ref "R_R") (pin "1") (pinfunction "1_1") (pintype "passive"))
      (node (ref "U1") (pin "47") (pinfunction "PWMH1/PA1_47") (pintype "bidirectional"))
      (node (ref "U5") (pin "10") (pinfunction "BIN2_10") (pintype "passive"))
    )
    (net (code "29") (name "/SLEEP") (class "Default")
      (node (ref "SLEEP") (pin "2") (pintype "passive"))
      (node (ref "U1") (pin "44") (pinfunction "PWMH2/PA2_44") (pintype "bidirectional"))
    )
    (net (code "30") (name "/SPCK") (class "Default")
      (node (ref "SPCK") (pin "1") (pinfunction "1_1") (pintype "passive"))
      (node (ref "U1") (pin "21") (pinfunction "SPCK/PWMH3/PA14_21") (pintype "bidirectional"))
      (node (ref "U7") (pin "5") (pinfunction "SCK_5") (pintype "passive"))
    )
    (net (code "31") (name "/SPI_CSN") (class "Default")
      (node (ref "SPI_CSN") (pin "1") (pinfunction "1_1") (pintype "passive"))
      (node (ref "U1") (pin "28") (pinfunction "PWMH0/PA11_28") (pintype "bidirectional"))
      (node (ref "U7") (pin "4") (pinfunction "CSN_4") (pintype "passive"))
    )
    (net (code "32") (name "/STAT0") (class "Default")
      (node (ref "R6") (pin "2") (pinfunction "2_2") (pintype "passive"))
      (node (ref "U1") (pin "42") (pinfunction "PWML2/PA30_42") (pintype "bidirectional"))
    )
    (net (code "33") (name "/STAT1") (class "Default")
      (node (ref "R7") (pin "2") (pinfunction "2_2") (pintype "passive"))
      (node (ref "U1") (pin "41") (pinfunction "PA29_41") (pintype "bidirectional"))
    )
    (net (code "34") (name "/SWCLK") (class "Default")
      (node (ref "H2") (pin "2") (pinfunction "2_2") (pintype "passive"))
      (node (ref "SWCLK") (pin "1") (pinfunction "1_1") (pintype "passive"))
      (node (ref "U1") (pin "53") (pinfunction "PB7/SWCLK/TCK_53") (pintype "bidirectional"))
    )
    (net (code "35") (name "/SWDIO") (class "Default")
      (node (ref "H2") (pin "4") (pinfunction "4_4") (pintype "passive"))
      (node (ref "SWDIO") (pin "1") (pinfunction "1_1") (pintype "passive"))
      (node (ref "U1") (pin "51") (pinfunction "PB6/SWDIO/TMS_51") (pintype "bidirectional"))
    )
    (net (code "36") (name "/USB_DETECT") (class "Default")
      (node (ref "R3") (pin "1") (pinfunction "1_1") (pintype "passive"))
      (node (ref "R4") (pin "1") (pinfunction "1_1") (pintype "passive"))
      (node (ref "U1") (pin "35") (pinfunction "RXD0/PA5_35") (pintype "bidirectional"))
    )
    (net (code "37") (name "/nRST") (class "Default")
      (node (ref "H2") (pin "1") (pinfunction "1_1") (pintype "passive"))
      (node (ref "U1") (pin "39") (pinfunction "~{NRST}_39") (pintype "bidirectional"))
      (node (ref "nRST") (pin "2") (pintype "passive"))
    )
    (net (code "38") (name "3V3A") (class "Default")
      (node (ref "3V3A") (pin "1") (pinfunction "1_1") (pintype "passive"))
      (node (ref "C19") (pin "2") (pinfunction "2_2") (pintype "passive"))
      (node (ref "C2") (pin "2") (pinfunction "2_2") (pintype "passive"))
      (node (ref "L2") (pin "1") (pinfunction "1_1") (pintype "passive"))
      (node (ref "U2") (pin "5") (pinfunction "OUT_5") (pintype "power_in"))
    )
    (net (code "39") (name "3V3D") (class "Default")
      (node (ref "3V3") (pin "1") (pinfunction "1_1") (pintype "passive"))
      (node (ref "C17") (pin "2") (pinfunction "2_2") (pintype "passive"))
      (node (ref "C20") (pin "2") (pinfunction "2_2") (pintype "passive"))
      (node (ref "C28") (pin "2") (pinfunction "2_2") (pintype "passive"))
      (node (ref "C5") (pin "2") (pinfunction "2_2") (pintype "passive"))
      (node (ref "C6") (pin "2") (pinfunction "2_2") (pintype "passive"))
      (node (ref "C7") (pin "2") (pinfunction "2_2") (pintype "passive"))
      (node (ref "C8") (pin "2") (pinfunction "2_2") (pintype "passive"))
      (node (ref "C9") (pin "2") (pinfunction "2_2") (pintype "passive"))
      (node (ref "H2") (pin "7") (pinfunction "7_7") (pintype "passive"))
      (node (ref "H2") (pin "8") (pinfunction "8_8") (pintype "passive"))
      (node (ref "H5") (pin "1") (pinfunction "1_1") (pintype "passive"))
      (node (ref "U1") (pin "1") (pinfunction "ADVREF_1") (pintype "input"))
      (node (ref "U1") (pin "18") (pinfunction "VDDIO_18") (pintype "power_in"))
      (node (ref "U1") (pin "45") (pinfunction "VDDIO_45") (pintype "power_in"))
      (node (ref "U1") (pin "58") (pinfunction "VDDIO_58") (pintype "power_in"))
      (node (ref "U1") (pin "7") (pinfunction "VDDIN_7") (pintype "power_in"))
      (node (ref "U4") (pin "5") (pinfunction "OUT_5") (pintype "power_in"))
      (node (ref "U6") (pin "6") (pinfunction "VCCB_6") (pintype "passive"))
    )
    (net (code "40") (name "5V_LP") (class "Default")
      (node (ref "5V") (pin "1") (pinfunction "1_1") (pintype "passive"))
      (node (ref "C1") (pin "2") (pinfunction "2_2") (pintype "passive"))
      (node (ref "C16") (pin "2") (pinfunction "2_2") (pintype "passive"))
      (node (ref "D2") (pin "1") (pinfunction "K_1") (pintype "passive"))
      (node (ref "D3") (pin "1") (pinfunction "K_1") (pintype "passive"))
      (node (ref "U2") (pin "1") (pinfunction "IN_1") (pintype "power_in"))
      (node (ref "U2") (pin "3") (pinfunction "EN_3") (pintype "input"))
      (node (ref "U4") (pin "1") (pinfunction "IN_1") (pintype "power_in"))
      (node (ref "U4") (pin "3") (pinfunction "EN_3") (pintype "input"))
    )
    (net (code "41") (name "5V_REG") (class "Default")
      (node (ref "C26") (pin "2") (pinfunction "2_2") (pintype "passive"))
      (node (ref "C27") (pin "2") (pinfunction "2_2") (pintype "passive"))
      (node (ref "C32") (pin "2") (pinfunction "2_2") (pintype "passive"))
      (node (ref "D2") (pin "2") (pinfunction "A_2") (pintype "passive"))
      (node (ref "H3") (pin "2") (pinfunction "2_2") (pintype "passive"))
      (node (ref "H4") (pin "2") (pinfunction "2_2") (pintype "passive"))
      (node (ref "L3") (pin "2") (pintype "passive"))
      (node (ref "LED_CON") (pin "1") (pinfunction "5V_1") (pintype "passive"))
      (node (ref "U3") (pin "5") (pinfunction "FB_5") (pintype "input"))
      (node (ref "U6") (pin "1") (pinfunction "VCCA_1") (pintype "passive"))
    )
    (net (code "42") (name "6V") (class "Default")
      (node (ref "C25") (pin "2") (pinfunction "2_2") (pintype "passive"))
      (node (ref "C29") (pin "2") (pinfunction "2_2") (pintype "passive"))
      (node (ref "H_B_PWR") (pin "1") (pinfunction "1_1") (pintype "passive"))
      (node (ref "Q4") (pin "2") (pinfunction "2_2") (pintype "passive"))
      (node (ref "R10") (pin "2") (pinfunction "2_2") (pintype "passive"))
      (node (ref "R20") (pin "2") (pinfunction "2_2") (pintype "passive"))
      (node (ref "R8") (pin "2") (pinfunction "2_2") (pintype "passive"))
      (node (ref "U3") (pin "2") (pinfunction "VIN_2") (pintype "input"))
    )
    (net (code "43") (name "GND") (class "Default")
      (node (ref "BAT") (pin "1") (pinfunction "GND_1") (pintype "passive"))
      (node (ref "BAT") (pin "3") (pinfunction "GND_3") (pintype "passive"))
      (node (ref "C1") (pin "1") (pinfunction "1_1") (pintype "passive"))
      (node (ref "C11") (pin "1") (pinfunction "1_1") (pintype "passive"))
      (node (ref "C12") (pin "2") (pinfunction "2_2") (pintype "passive"))
      (node (ref "C13") (pin "2") (pinfunction "2_2") (pintype "passive"))
      (node (ref "C14") (pin "2") (pinfunction "2_2") (pintype "passive"))
      (node (ref "C15") (pin "2") (pinfunction "2_2") (pintype "passive"))
      (node (ref "C16") (pin "1") (pinfunction "1_1") (pintype "passive"))
      (node (ref "C17") (pin "1") (pinfunction "1_1") (pintype "passive"))
      (node (ref "C19") (pin "1") (pinfunction "1_1") (pintype "passive"))
      (node (ref "C2") (pin "1") (pinfunction "1_1") (pintype "passive"))
      (node (ref "C20") (pin "1") (pinfunction "1_1") (pintype "passive"))
      (node (ref "C21") (pin "1") (pinfunction "1_1") (pintype "passive"))
      (node (ref "C22") (pin "2") (pinfunction "2_2") (pintype "passive"))
      (node (ref "C23") (pin "2") (pinfunction "2_2") (pintype "passive"))
      (node (ref "C25") (pin "1") (pinfunction "1_1") (pintype "passive"))
      (node (ref "C26") (pin "1") (pinfunction "1_1") (pintype "passive"))
      (node (ref "C27") (pin "1") (pinfunction "1_1") (pintype "passive"))
      (node (ref "C28") (pin "1") (pinfunction "1_1") (pintype "passive"))
      (node (ref "C29") (pin "1") (pinfunction "1_1") (pintype "passive"))
      (node (ref "C3") (pin "1") (pinfunction "1_1") (pintype "passive"))
      (node (ref "C30") (pin "1") (pinfunction "1_1") (pintype "passive"))
      (node (ref "C31") (pin "1") (pinfunction "1_1") (pintype "passive"))
      (node (ref "C32") (pin "1") (pinfunction "1_1") (pintype "passive"))
      (node (ref "C33") (pin "1") (pinfunction "1_1") (pintype "passive"))
      (node (ref "C34") (pin "1") (pinfunction "1_1") (pintype "passive"))
      (node (ref "C4") (pin "1") (pinfunction "1_1") (pintype "passive"))
      (node (ref "C5") (pin "1") (pinfunction "1_1") (pintype "passive"))
      (node (ref "C6") (pin "1") (pinfunction "1_1") (pintype "passive"))
      (node (ref "C7") (pin "1") (pinfunction "1_1") (pintype "passive"))
      (node (ref "C8") (pin "1") (pinfunction "1_1") (pintype "passive"))
      (node (ref "C9") (pin "1") (pinfunction "1_1") (pintype "passive"))
      (node (ref "CH_1") (pin "2") (pinfunction "2_2") (pintype "passive"))
      (node (ref "CH_2") (pin "2") (pinfunction "2_2") (pintype "passive"))
      (node (ref "CH_3") (pin "2") (pinfunction "2_2") (pintype "passive"))
      (node (ref "CH_4") (pin "2") (pinfunction "2_2") (pintype "passive"))
      (node (ref "D1") (pin "1") (pinfunction "A_1") (pintype "passive"))
      (node (ref "GND") (pin "1") (pinfunction "1_1") (pintype "passive"))
      (node (ref "H1") (pin "5") (pinfunction "GND_5") (pintype "passive"))
      (node (ref "H1") (pin "6") (pinfunction "SHLD_6") (pintype "passive"))
      (node (ref "H2") (pin "5") (pinfunction "5_5") (pintype "passive"))
      (node (ref "H2") (pin "6") (pinfunction "6_6") (pintype "passive"))
      (node (ref "H5") (pin "3") (pinfunction "3_3") (pintype "passive"))
      (node (ref "H6") (pin "2") (pinfunction "2_2") (pintype "passive"))
      (node (ref "LED_CON") (pin "3") (pinfunction "COM_3") (pintype "passive"))
      (node (ref "Q4") (pin "1") (pinfunction "1_1") (pintype "passive"))
      (node (ref "R12") (pin "1") (pinfunction "1_1") (pintype "passive"))
      (node (ref "R14") (pin "2") (pinfunction "2_2") (pintype "passive"))
      (node (ref "R15") (pin "2") (pinfunction "2_2") (pintype "passive"))
      (node (ref "R23") (pin "1") (pinfunction "1_1") (pintype "passive"))
      (node (ref "R4") (pin "2") (pinfunction "2_2") (pintype "passive"))
      (node (ref "R5") (pin "1") (pinfunction "1_1") (pintype "passive"))
      (node (ref "R9") (pin "1") (pinfunction "1_1") (pintype "passive"))
      (node (ref "SLEEP") (pin "1") (pintype "passive"))
      (node (ref "STAT_1") (pin "1") (pinfunction "K_1") (pintype "passive"))
      (node (ref "STAT_2") (pin "1") (pinfunction "K_1") (pintype "passive"))
      (node (ref "T1") (pin "2") (pinfunction "2_2") (pintype "passive"))
      (node (ref "T2") (pin "2") (pinfunction "2_2") (pintype "passive"))
      (node (ref "U1") (pin "17") (pinfunction "GND_17") (pintype "power_in"))
      (node (ref "U1") (pin "2") (pinfunction "GND_2") (pintype "power_in"))
      (node (ref "U1") (pin "46") (pinfunction "GND_46") (pintype "power_in"))
      (node (ref "U1") (pin "60") (pinfunction "GND_60") (pintype "power_in"))
      (node (ref "U2") (pin "2") (pinfunction "GND_2") (pintype "power_in"))
      (node (ref "U3") (pin "7") (pinfunction "GND_7") (pintype "power_in"))
      (node (ref "U3") (pin "EPAD") (pinfunction "EPAD_EPAD") (pintype "passive"))
      (node (ref "U4") (pin "2") (pinfunction "GND_2") (pintype "power_in"))
      (node (ref "U5") (pin "13") (pinfunction "GND_13") (pintype "passive"))
      (node (ref "U5") (pin "17") (pinfunction "PAD_17") (pintype "passive"))
      (node (ref "U5") (pin "3") (pinfunction "AISEN_3") (pintype "passive"))
      (node (ref "U5") (pin "6") (pinfunction "BISEN_6") (pintype "passive"))
      (node (ref "U6") (pin "2") (pinfunction "GND_2") (pintype "passive"))
      (node (ref "U6") (pin "5") (pinfunction "DIR_5") (pintype "passive"))
      (node (ref "U7") (pin "2") (pinfunction "GND_2") (pintype "passive"))
      (node (ref "nRST") (pin "1") (pintype "passive"))
    )
    (net (code "44") (name "Net-(BAT-VBATT)") (class "Default")
      (node (ref "BAT") (pin "2") (pinfunction "VBATT_2") (pintype "passive"))
      (node (ref "C33") (pin "2") (pinfunction "2_2") (pintype "passive"))
      (node (ref "C34") (pin "2") (pinfunction "2_2") (pintype "passive"))
      (node (ref "F1") (pin "1") (pinfunction "1_1") (pintype "passive"))
    )
    (net (code "45") (name "Net-(C10-Pad1)") (class "Default")
      (node (ref "C10") (pin "1") (pinfunction "1_1") (pintype "passive"))
      (node (ref "R5") (pin "2") (pinfunction "2_2") (pintype "passive"))
    )
    (net (code "46") (name "Net-(D1-K)") (class "Default")
      (node (ref "C24") (pin "1") (pinfunction "1_1") (pintype "passive"))
      (node (ref "D1") (pin "2") (pinfunction "K_2") (pintype "passive"))
      (node (ref "L3") (pin "1") (pintype "passive"))
      (node (ref "U3") (pin "8") (pinfunction "SW_8") (pintype "output"))
    )
    (net (code "47") (name "Net-(F1-Pad2)") (class "Default")
      (node (ref "F1") (pin "2") (pinfunction "2_2") (pintype "passive"))
      (node (ref "Q4") (pin "3") (pinfunction "3_3") (pintype "passive"))
    )
    (net (code "48") (name "Net-(H3-Pad1)") (class "Default")
      (node (ref "H3") (pin "1") (pinfunction "1_1") (pintype "passive"))
      (node (ref "T2") (pin "3") (pinfunction "3_3") (pintype "passive"))
    )
    (net (code "49") (name "Net-(H4-Pad1)") (class "Default")
      (node (ref "H4") (pin "1") (pinfunction "1_1") (pintype "passive"))
      (node (ref "T1") (pin "3") (pinfunction "3_3") (pintype "passive"))
    )
    (net (code "50") (name "Net-(R11-Pad2)") (class "Default")
      (node (ref "R11") (pin "2") (pinfunction "2_2") (pintype "passive"))
      (node (ref "R14") (pin "1") (pinfunction "1_1") (pintype "passive"))
      (node (ref "T2") (pin "1") (pinfunction "1_1") (pintype "passive"))
    )
    (net (code "51") (name "Net-(R13-Pad2)") (class "Default")
      (node (ref "R13") (pin "2") (pinfunction "2_2") (pintype "passive"))
      (node (ref "R15") (pin "1") (pinfunction "1_1") (pintype "passive"))
      (node (ref "T1") (pin "1") (pinfunction "1_1") (pintype "passive"))
    )
    (net (code "52") (name "Net-(STAT_1-A)") (class "Default")
      (node (ref "R6") (pin "1") (pinfunction "1_1") (pintype "passive"))
      (node (ref "STAT_1") (pin "2") (pinfunction "A_2") (pintype "passive"))
    )
    (net (code "53") (name "Net-(STAT_2-A)") (class "Default")
      (node (ref "R7") (pin "1") (pinfunction "1_1") (pintype "passive"))
      (node (ref "STAT_2") (pin "2") (pinfunction "A_2") (pintype "passive"))
    )
    (net (code "54") (name "Net-(U1A-PB8{slash}XOUT)") (class "Default")
      (node (ref "C4") (pin "2") (pinfunction "2_2") (pintype "passive"))
      (node (ref "U1") (pin "61") (pinfunction "PB8/XOUT_61") (pintype "bidirectional"))
      (node (ref "Y1") (pin "1") (pinfunction "OSC1_1") (pintype "passive"))
    )
    (net (code "55") (name "Net-(U1A-PB9{slash}XIN)") (class "Default")
      (node (ref "C3") (pin "2") (pinfunction "2_2") (pintype "passive"))
      (node (ref "U1") (pin "62") (pinfunction "PB9/XIN_62") (pintype "bidirectional"))
      (node (ref "Y1") (pin "3") (pinfunction "OSC2_3") (pintype "passive"))
    )
    (net (code "56") (name "Net-(U1A-PB10{slash}DDM)") (class "Default")
      (node (ref "R2") (pin "2") (pinfunction "2_2") (pintype "passive"))
      (node (ref "U1") (pin "56") (pinfunction "PB10/DDM_56") (pintype "bidirectional"))
    )
    (net (code "57") (name "Net-(U1A-PB11{slash}DDP)") (class "Default")
      (node (ref "R1") (pin "2") (pinfunction "2_2") (pintype "passive"))
      (node (ref "U1") (pin "57") (pinfunction "PB11/DDP_57") (pintype "bidirectional"))
    )
    (net (code "58") (name "Net-(U1A-PB12{slash}ERASE)") (class "Default")
      (node (ref "ERASE") (pin "1") (pinfunction "1_1") (pintype "passive"))
      (node (ref "U1") (pin "55") (pinfunction "PB12/ERASE_55") (pintype "bidirectional"))
    )
    (net (code "59") (name "Net-(U1B-VDDOUT)") (class "Default")
      (node (ref "C12") (pin "1") (pinfunction "1_1") (pintype "passive"))
      (node (ref "C13") (pin "1") (pinfunction "1_1") (pintype "passive"))
      (node (ref "C14") (pin "1") (pinfunction "1_1") (pintype "passive"))
      (node (ref "C15") (pin "1") (pinfunction "1_1") (pintype "passive"))
      (node (ref "L1") (pin "2") (pinfunction "2_2") (pintype "passive"))
      (node (ref "U1") (pin "12") (pinfunction "VDDCORE_12") (pintype "power_in"))
      (node (ref "U1") (pin "24") (pinfunction "VDDCORE_24") (pintype "power_in"))
      (node (ref "U1") (pin "54") (pinfunction "VDDCORE_54") (pintype "power_in"))
      (node (ref "U1") (pin "8") (pinfunction "VDDOUT_8") (pintype "power_in"))
    )
    (net (code "60") (name "Net-(U1B-VDDPLL)") (class "Default")
      (node (ref "C10") (pin "2") (pinfunction "2_2") (pintype "passive"))
      (node (ref "C11") (pin "2") (pinfunction "2_2") (pintype "passive"))
      (node (ref "L1") (pin "1") (pinfunction "1_1") (pintype "passive"))
      (node (ref "U1") (pin "64") (pinfunction "VDDPLL_64") (pintype "power_in"))
    )
    (net (code "61") (name "Net-(U3-BST)") (class "Default")
      (node (ref "C24") (pin "2") (pinfunction "2_2") (pintype "passive"))
      (node (ref "U3") (pin "1") (pinfunction "BST_1") (pintype "passive"))
    )
    (net (code "62") (name "Net-(U3-EN)") (class "Default")
      (node (ref "R10") (pin "1") (pinfunction "1_1") (pintype "passive"))
      (node (ref "R23") (pin "2") (pinfunction "2_2") (pintype "passive"))
      (node (ref "U3") (pin "3") (pinfunction "EN_3") (pintype "input"))
    )
    (net (code "63") (name "Net-(U3-PGOOD)") (class "Default")
      (node (ref "R20") (pin "1") (pinfunction "1_1") (pintype "passive"))
      (node (ref "U3") (pin "4") (pinfunction "PGOOD_4") (pintype "output"))
    )
    (net (code "64") (name "Net-(U5-VCP)") (class "Default")
      (node (ref "C18") (pin "1") (pinfunction "1_1") (pintype "passive"))
      (node (ref "U5") (pin "11") (pinfunction "VCP_11") (pintype "passive"))
    )
    (net (code "65") (name "Net-(U5-VINT)") (class "Default")
      (node (ref "C23") (pin "1") (pinfunction "1_1") (pintype "passive"))
      (node (ref "U5") (pin "14") (pinfunction "VINT_14") (pintype "passive"))
    )
    (net (code "66") (name "Net-(U5-VM)") (class "Default")
      (node (ref "C18") (pin "2") (pinfunction "2_2") (pintype "passive"))
      (node (ref "C22") (pin "1") (pinfunction "1_1") (pintype "passive"))
      (node (ref "H_B_PWR") (pin "2") (pinfunction "2_2") (pintype "passive"))
      (node (ref "U5") (pin "12") (pinfunction "VM_12") (pintype "passive"))
    )
    (net (code "67") (name "Net-(U7-VCC)") (class "Default")
      (node (ref "C21") (pin "2") (pinfunction "2_2") (pintype "passive"))
      (node (ref "L2") (pin "2") (pinfunction "2_2") (pintype "passive"))
      (node (ref "U7") (pin "1") (pinfunction "VCC_1") (pintype "passive"))
    )
    (net (code "68") (name "VBUS") (class "Default")
      (node (ref "C30") (pin "2") (pinfunction "2_2") (pintype "passive"))
      (node (ref "C31") (pin "2") (pinfunction "2_2") (pintype "passive"))
      (node (ref "D3") (pin "2") (pinfunction "A_2") (pintype "passive"))
      (node (ref "H1") (pin "1") (pinfunction "VBUS_1") (pintype "power_in"))
      (node (ref "R3") (pin "2") (pinfunction "2_2") (pintype "passive"))
    )
    (net (code "69") (name "unconnected-(H1-ID-Pad4)") (class "Default")
      (node (ref "H1") (pin "4") (pinfunction "ID_4") (pintype "power_in+no_connect"))
    )
    (net (code "70") (name "unconnected-(H2-Pad3)") (class "Default")
      (node (ref "H2") (pin "3") (pinfunction "3_3") (pintype "passive+no_connect"))
    )
    (net (code "71") (name "unconnected-(H2-Pad9)") (class "Default")
      (node (ref "H2") (pin "9") (pinfunction "9_9") (pintype "passive+no_connect"))
    )
    (net (code "72") (name "unconnected-(H2-Pad10)") (class "Default")
      (node (ref "H2") (pin "10") (pinfunction "10_10") (pintype "passive+no_connect"))
    )
    (net (code "73") (name "unconnected-(U1A-AD2{slash}PWML0{slash}PA19-Pad13)") (class "Default")
      (node (ref "U1") (pin "13") (pinfunction "AD2/PWML0/PA19_13") (pintype "bidirectional+no_connect"))
    )
    (net (code "74") (name "unconnected-(U1A-AD8{slash}RXD1{slash}PA21-Pad11)") (class "Default")
      (node (ref "U1") (pin "11") (pinfunction "AD8/RXD1/PA21_11") (pintype "bidirectional"))
    )
    (net (code "75") (name "unconnected-(U1A-AD9{slash}TXD1{slash}PA22-Pad14)") (class "Default")
      (node (ref "U1") (pin "14") (pinfunction "AD9/TXD1/PA22_14") (pintype "bidirectional+no_connect"))
    )
    (net (code "76") (name "unconnected-(U1A-JTAGSEL-Pad50)") (class "Default")
      (node (ref "U1") (pin "50") (pinfunction "JTAGSEL_50") (pintype "input+no_connect"))
    )
    (net (code "77") (name "unconnected-(U1A-PA8-Pad31)") (class "Default")
      (node (ref "U1") (pin "31") (pinfunction "PA8_31") (pintype "bidirectional+no_connect"))
    )
    (net (code "78") (name "unconnected-(U1A-PA27-Pad37)") (class "Default")
      (node (ref "U1") (pin "37") (pinfunction "PA27_37") (pintype "bidirectional+no_connect"))
    )
    (net (code "79") (name "unconnected-(U1A-PA28-Pad38)") (class "Default")
      (node (ref "U1") (pin "38") (pinfunction "PA28_38") (pintype "bidirectional+no_connect"))
    )
    (net (code "80") (name "unconnected-(U1A-PA31-Pad52)") (class "Default")
      (node (ref "U1") (pin "52") (pinfunction "PA31_52") (pintype "bidirectional+no_connect"))
    )
    (net (code "81") (name "unconnected-(U1A-PB1{slash}PWMH1{slash}AD5-Pad4)") (class "Default")
      (node (ref "U1") (pin "4") (pinfunction "PB1/PWMH1/AD5_4") (pintype "bidirectional+no_connect"))
    )
    (net (code "82") (name "unconnected-(U1A-PB4{slash}PWMH2{slash}TDI-Pad33)") (class "Default")
      (node (ref "U1") (pin "33") (pinfunction "PB4/PWMH2/TDI_33") (pintype "bidirectional+no_connect"))
    )
    (net (code "83") (name "unconnected-(U1A-PB5{slash}PWML0{slash}TDO-Pad49)") (class "Default")
      (node (ref "U1") (pin "49") (pinfunction "PB5/PWML0/TDO_49") (pintype "bidirectional+no_connect"))
    )
    (net (code "84") (name "unconnected-(U1A-PWMH1{slash}PA24-Pad23)") (class "Default")
      (node (ref "U1") (pin "23") (pinfunction "PWMH1/PA24_23") (pintype "bidirectional+no_connect"))
    )
    (net (code "85") (name "unconnected-(U1A-TST-Pad40)") (class "Default")
      (node (ref "U1") (pin "40") (pinfunction "TST_40") (pintype "input+no_connect"))
    )
    (net (code "86") (name "unconnected-(U1A-TWCK0{slash}PA4-Pad36)") (class "Default")
      (node (ref "U1") (pin "36") (pinfunction "TWCK0/PA4_36") (pintype "bidirectional+no_connect"))
    )
    (net (code "87") (name "unconnected-(U1A-TWD0{slash}PA3-Pad43)") (class "Default")
      (node (ref "U1") (pin "43") (pinfunction "TWD0/PA3_43") (pintype "bidirectional+no_connect"))
    )
    (net (code "88") (name "unconnected-(U1A-TXD0{slash}PA6-Pad34)") (class "Default")
      (node (ref "U1") (pin "34") (pinfunction "TXD0/PA6_34") (pintype "bidirectional+no_connect"))
    )
    (net (code "89") (name "unconnected-(U2-BYP-Pad4)") (class "Default")
      (node (ref "U2") (pin "4") (pinfunction "BYP_4") (pintype "passive+no_connect"))
    )
    (net (code "90") (name "unconnected-(U3-NC-Pad6)") (class "Default")
      (node (ref "U3") (pin "6") (pinfunction "NC_6") (pintype "passive+no_connect"))
    )
    (net (code "91") (name "unconnected-(U4-BYP-Pad4)") (class "Default")
      (node (ref "U4") (pin "4") (pinfunction "BYP_4") (pintype "passive+no_connect"))
    )
  )
)
